# Backplane_PCB_Connector.net
KiCad netlist of a schematic drawn in Altium Designer
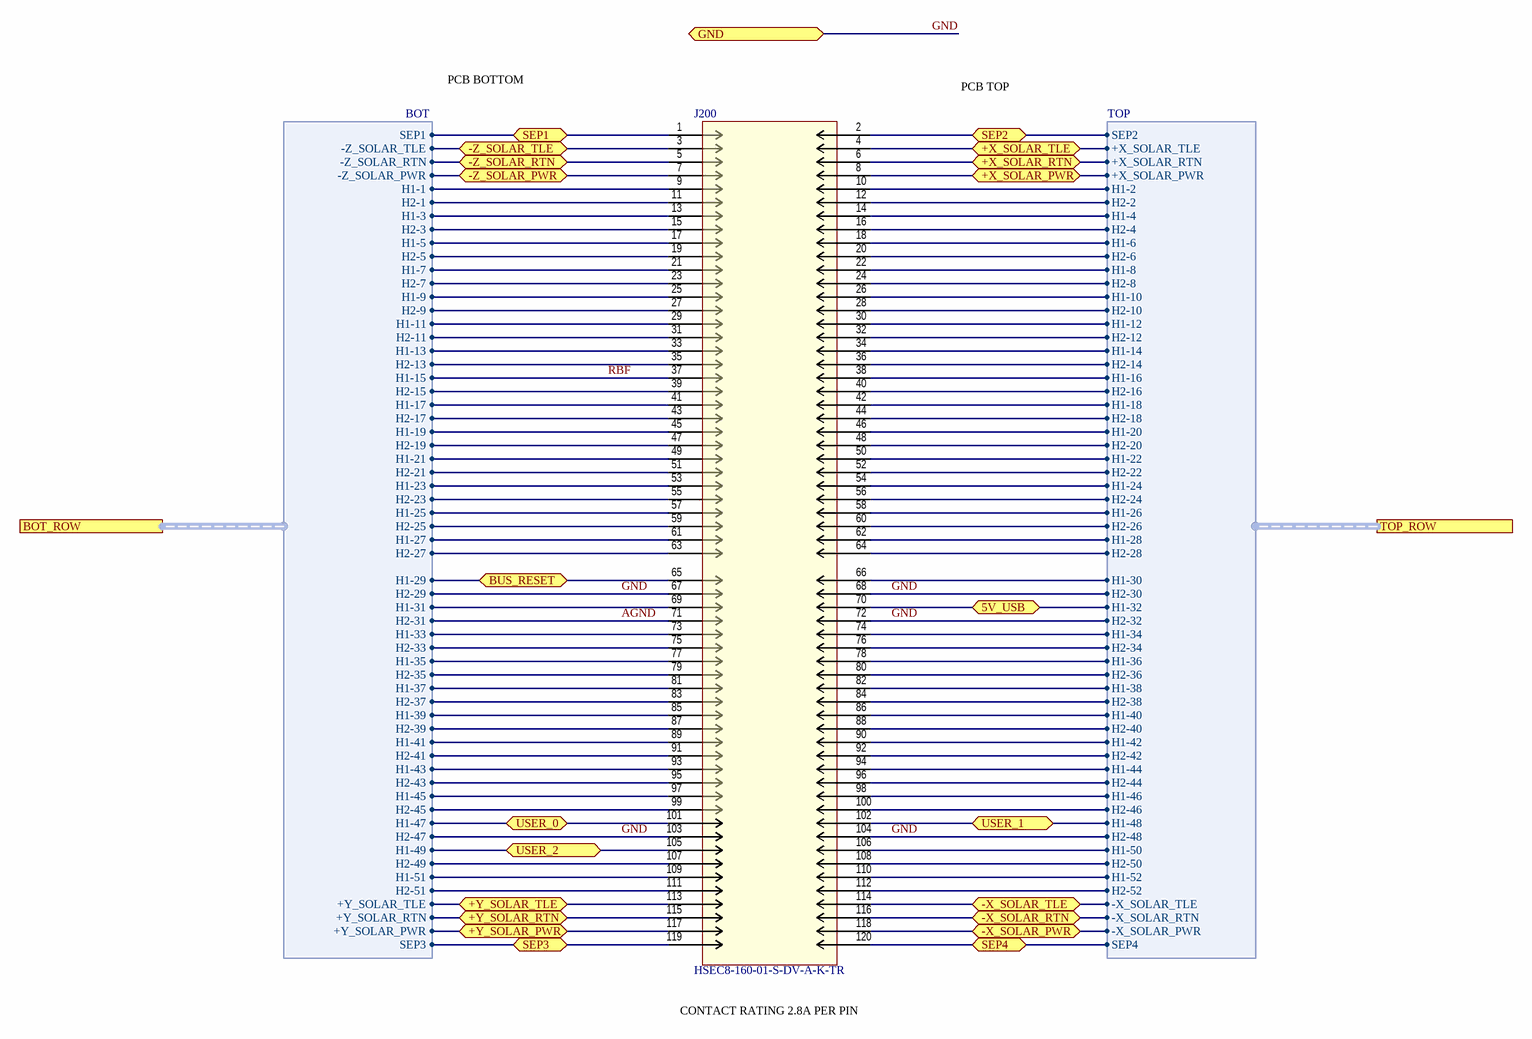
[diagram p0: Backplane PCB Connector.SchDoc]

(export (version "E")
  (design (tool "Eeschema 10.0.6"))
  (components
    (comp (ref "J200")
      (value "HSEC8-160-01-S-DV-A-K-TR")
      (footprint "HSEC8-160-01-S-DV-A-K-TR")
      (description "120 Position Female Connector Non Specified - Dual Edge Gold 0.031\" (0.80mm) Black")
      (fields (field (name "MANUFACTURER PART NUMBER 1") "HSEC8-160-01-S-DV-A-K-TR"))
      (libsource (lib "CubeSat-Backplane") (part "HSEC8-160-01-S-DV-A-K-TR"))
    )
  )
  (nets
    (net (code "3") (name "/+X_SOLAR_PWR") (class "Default")
      (node (ref "J200") (pin "8") (pinfunction "8_8") (pintype "passive"))
    )
    (net (code "4") (name "/+X_SOLAR_RTN") (class "Default")
      (node (ref "J200") (pin "6") (pinfunction "6_6") (pintype "passive"))
    )
    (net (code "5") (name "/+X_SOLAR_TLE") (class "Default")
      (node (ref "J200") (pin "4") (pinfunction "4_4") (pintype "passive"))
    )
    (net (code "6") (name "/+Y_SOLAR_PWR") (class "Default")
      (node (ref "J200") (pin "117") (pinfunction "117_117") (pintype "passive"))
    )
    (net (code "7") (name "/+Y_SOLAR_RTN") (class "Default")
      (node (ref "J200") (pin "115") (pinfunction "115_115") (pintype "passive"))
    )
    (net (code "8") (name "/+Y_SOLAR_TLE") (class "Default")
      (node (ref "J200") (pin "113") (pinfunction "113_113") (pintype "passive"))
    )
    (net (code "9") (name "/-X_SOLAR_PWR") (class "Default")
      (node (ref "J200") (pin "118") (pinfunction "118_118") (pintype "passive"))
    )
    (net (code "10") (name "/-X_SOLAR_RTN") (class "Default")
      (node (ref "J200") (pin "116") (pinfunction "116_116") (pintype "passive"))
    )
    (net (code "11") (name "/-X_SOLAR_TLE") (class "Default")
      (node (ref "J200") (pin "114") (pinfunction "114_114") (pintype "passive"))
    )
    (net (code "12") (name "/-Z_SOLAR_PWR") (class "Default")
      (node (ref "J200") (pin "7") (pinfunction "7_7") (pintype "passive"))
    )
    (net (code "13") (name "/-Z_SOLAR_RTN") (class "Default")
      (node (ref "J200") (pin "5") (pinfunction "5_5") (pintype "passive"))
    )
    (net (code "14") (name "/-Z_SOLAR_TLE") (class "Default")
      (node (ref "J200") (pin "3") (pinfunction "3_3") (pintype "passive"))
    )
    (net (code "15") (name "/5V_USB") (class "Default")
      (node (ref "J200") (pin "70") (pinfunction "70_70") (pintype "passive"))
    )
    (net (code "16") (name "/AGND") (class "Default")
      (node (ref "J200") (pin "71") (pinfunction "71_71") (pintype "passive"))
    )
    (net (code "17") (name "/BUS_RESET") (class "Default")
      (node (ref "J200") (pin "65") (pinfunction "65_65") (pintype "passive"))
    )
    (net (code "18") (name "/GND") (class "Default")
      (node (ref "J200") (pin "103") (pinfunction "103_103") (pintype "passive"))
      (node (ref "J200") (pin "104") (pinfunction "104_104") (pintype "passive"))
      (node (ref "J200") (pin "67") (pinfunction "67_67") (pintype "passive"))
      (node (ref "J200") (pin "68") (pinfunction "68_68") (pintype "passive"))
      (node (ref "J200") (pin "72") (pinfunction "72_72") (pintype "passive"))
    )
    (net (code "19") (name "/H1-1") (class "Default")
      (node (ref "J200") (pin "9") (pinfunction "9_9") (pintype "passive"))
    )
    (net (code "20") (name "/H1-2") (class "Default")
      (node (ref "J200") (pin "10") (pinfunction "10_10") (pintype "passive"))
    )
    (net (code "21") (name "/H1-3") (class "Default")
      (node (ref "J200") (pin "13") (pinfunction "13_13") (pintype "passive"))
    )
    (net (code "22") (name "/H1-4") (class "Default")
      (node (ref "J200") (pin "14") (pinfunction "14_14") (pintype "passive"))
    )
    (net (code "23") (name "/H1-5") (class "Default")
      (node (ref "J200") (pin "17") (pinfunction "17_17") (pintype "passive"))
    )
    (net (code "24") (name "/H1-6") (class "Default")
      (node (ref "J200") (pin "18") (pinfunction "18_18") (pintype "passive"))
    )
    (net (code "25") (name "/H1-7") (class "Default")
      (node (ref "J200") (pin "21") (pinfunction "21_21") (pintype "passive"))
    )
    (net (code "26") (name "/H1-8") (class "Default")
      (node (ref "J200") (pin "22") (pinfunction "22_22") (pintype "passive"))
    )
    (net (code "27") (name "/H1-9") (class "Default")
      (node (ref "J200") (pin "25") (pinfunction "25_25") (pintype "passive"))
    )
    (net (code "28") (name "/H1-10") (class "Default")
      (node (ref "J200") (pin "26") (pinfunction "26_26") (pintype "passive"))
    )
    (net (code "29") (name "/H1-11") (class "Default")
      (node (ref "J200") (pin "29") (pinfunction "29_29") (pintype "passive"))
    )
    (net (code "30") (name "/H1-12") (class "Default")
      (node (ref "J200") (pin "30") (pinfunction "30_30") (pintype "passive"))
    )
    (net (code "31") (name "/H1-13") (class "Default")
      (node (ref "J200") (pin "33") (pinfunction "33_33") (pintype "passive"))
    )
    (net (code "32") (name "/H1-14") (class "Default")
      (node (ref "J200") (pin "34") (pinfunction "34_34") (pintype "passive"))
    )
    (net (code "33") (name "/H1-16") (class "Default")
      (node (ref "J200") (pin "38") (pinfunction "38_38") (pintype "passive"))
    )
    (net (code "34") (name "/H1-17") (class "Default")
      (node (ref "J200") (pin "41") (pinfunction "41_41") (pintype "passive"))
    )
    (net (code "35") (name "/H1-18") (class "Default")
      (node (ref "J200") (pin "42") (pinfunction "42_42") (pintype "passive"))
    )
    (net (code "36") (name "/H1-19") (class "Default")
      (node (ref "J200") (pin "45") (pinfunction "45_45") (pintype "passive"))
    )
    (net (code "37") (name "/H1-20") (class "Default")
      (node (ref "J200") (pin "46") (pinfunction "46_46") (pintype "passive"))
    )
    (net (code "38") (name "/H1-21") (class "Default")
      (node (ref "J200") (pin "49") (pinfunction "49_49") (pintype "passive"))
    )
    (net (code "39") (name "/H1-22") (class "Default")
      (node (ref "J200") (pin "50") (pinfunction "50_50") (pintype "passive"))
    )
    (net (code "40") (name "/H1-23") (class "Default")
      (node (ref "J200") (pin "53") (pinfunction "53_53") (pintype "passive"))
    )
    (net (code "41") (name "/H1-24") (class "Default")
      (node (ref "J200") (pin "54") (pinfunction "54_54") (pintype "passive"))
    )
    (net (code "42") (name "/H1-25") (class "Default")
      (node (ref "J200") (pin "57") (pinfunction "57_57") (pintype "passive"))
    )
    (net (code "43") (name "/H1-26") (class "Default")
      (node (ref "J200") (pin "58") (pinfunction "58_58") (pintype "passive"))
    )
    (net (code "44") (name "/H1-27") (class "Default")
      (node (ref "J200") (pin "61") (pinfunction "61_61") (pintype "passive"))
    )
    (net (code "45") (name "/H1-28") (class "Default")
      (node (ref "J200") (pin "62") (pinfunction "62_62") (pintype "passive"))
    )
    (net (code "46") (name "/H1-30") (class "Default")
      (node (ref "J200") (pin "66") (pinfunction "66_66") (pintype "passive"))
    )
    (net (code "47") (name "/H1-31") (class "Default")
      (node (ref "J200") (pin "69") (pinfunction "69_69") (pintype "passive"))
    )
    (net (code "48") (name "/H1-33") (class "Default")
      (node (ref "J200") (pin "73") (pinfunction "73_73") (pintype "passive"))
    )
    (net (code "49") (name "/H1-34") (class "Default")
      (node (ref "J200") (pin "74") (pinfunction "74_74") (pintype "passive"))
    )
    (net (code "50") (name "/H1-35") (class "Default")
      (node (ref "J200") (pin "77") (pinfunction "77_77") (pintype "passive"))
    )
    (net (code "51") (name "/H1-36") (class "Default")
      (node (ref "J200") (pin "78") (pinfunction "78_78") (pintype "passive"))
    )
    (net (code "52") (name "/H1-37") (class "Default")
      (node (ref "J200") (pin "81") (pinfunction "81_81") (pintype "passive"))
    )
    (net (code "53") (name "/H1-38") (class "Default")
      (node (ref "J200") (pin "82") (pinfunction "82_82") (pintype "passive"))
    )
    (net (code "54") (name "/H1-39") (class "Default")
      (node (ref "J200") (pin "85") (pinfunction "85_85") (pintype "passive"))
    )
    (net (code "55") (name "/H1-40") (class "Default")
      (node (ref "J200") (pin "86") (pinfunction "86_86") (pintype "passive"))
    )
    (net (code "56") (name "/H1-41") (class "Default")
      (node (ref "J200") (pin "89") (pinfunction "89_89") (pintype "passive"))
    )
    (net (code "57") (name "/H1-42") (class "Default")
      (node (ref "J200") (pin "90") (pinfunction "90_90") (pintype "passive"))
    )
    (net (code "58") (name "/H1-43") (class "Default")
      (node (ref "J200") (pin "93") (pinfunction "93_93") (pintype "passive"))
    )
    (net (code "59") (name "/H1-44") (class "Default")
      (node (ref "J200") (pin "94") (pinfunction "94_94") (pintype "passive"))
    )
    (net (code "60") (name "/H1-45") (class "Default")
      (node (ref "J200") (pin "97") (pinfunction "97_97") (pintype "passive"))
    )
    (net (code "61") (name "/H1-46") (class "Default")
      (node (ref "J200") (pin "98") (pinfunction "98_98") (pintype "passive"))
    )
    (net (code "62") (name "/H1-50") (class "Default")
      (node (ref "J200") (pin "106") (pinfunction "106_106") (pintype "passive"))
    )
    (net (code "63") (name "/H1-51") (class "Default")
      (node (ref "J200") (pin "109") (pinfunction "109_109") (pintype "passive"))
    )
    (net (code "64") (name "/H1-52") (class "Default")
      (node (ref "J200") (pin "110") (pinfunction "110_110") (pintype "passive"))
    )
    (net (code "65") (name "/H2-1") (class "Default")
      (node (ref "J200") (pin "11") (pinfunction "11_11") (pintype "passive"))
    )
    (net (code "66") (name "/H2-2") (class "Default")
      (node (ref "J200") (pin "12") (pinfunction "12_12") (pintype "passive"))
    )
    (net (code "67") (name "/H2-3") (class "Default")
      (node (ref "J200") (pin "15") (pinfunction "15_15") (pintype "passive"))
    )
    (net (code "68") (name "/H2-4") (class "Default")
      (node (ref "J200") (pin "16") (pinfunction "16_16") (pintype "passive"))
    )
    (net (code "69") (name "/H2-5") (class "Default")
      (node (ref "J200") (pin "19") (pinfunction "19_19") (pintype "passive"))
    )
    (net (code "70") (name "/H2-6") (class "Default")
      (node (ref "J200") (pin "20") (pinfunction "20_20") (pintype "passive"))
    )
    (net (code "71") (name "/H2-7") (class "Default")
      (node (ref "J200") (pin "23") (pinfunction "23_23") (pintype "passive"))
    )
    (net (code "72") (name "/H2-8") (class "Default")
      (node (ref "J200") (pin "24") (pinfunction "24_24") (pintype "passive"))
    )
    (net (code "73") (name "/H2-9") (class "Default")
      (node (ref "J200") (pin "27") (pinfunction "27_27") (pintype "passive"))
    )
    (net (code "74") (name "/H2-10") (class "Default")
      (node (ref "J200") (pin "28") (pinfunction "28_28") (pintype "passive"))
    )
    (net (code "75") (name "/H2-11") (class "Default")
      (node (ref "J200") (pin "31") (pinfunction "31_31") (pintype "passive"))
    )
    (net (code "76") (name "/H2-12") (class "Default")
      (node (ref "J200") (pin "32") (pinfunction "32_32") (pintype "passive"))
    )
    (net (code "77") (name "/H2-13") (class "Default")
      (node (ref "J200") (pin "35") (pinfunction "35_35") (pintype "passive"))
    )
    (net (code "78") (name "/H2-14") (class "Default")
      (node (ref "J200") (pin "36") (pinfunction "36_36") (pintype "passive"))
    )
    (net (code "79") (name "/H2-15") (class "Default")
      (node (ref "J200") (pin "39") (pinfunction "39_39") (pintype "passive"))
    )
    (net (code "80") (name "/H2-16") (class "Default")
      (node (ref "J200") (pin "40") (pinfunction "40_40") (pintype "passive"))
    )
    (net (code "81") (name "/H2-17") (class "Default")
      (node (ref "J200") (pin "43") (pinfunction "43_43") (pintype "passive"))
    )
    (net (code "82") (name "/H2-18") (class "Default")
      (node (ref "J200") (pin "44") (pinfunction "44_44") (pintype "passive"))
    )
    (net (code "83") (name "/H2-19") (class "Default")
      (node (ref "J200") (pin "47") (pinfunction "47_47") (pintype "passive"))
    )
    (net (code "84") (name "/H2-20") (class "Default")
      (node (ref "J200") (pin "48") (pinfunction "48_48") (pintype "passive"))
    )
    (net (code "85") (name "/H2-21") (class "Default")
      (node (ref "J200") (pin "51") (pinfunction "51_51") (pintype "passive"))
    )
    (net (code "86") (name "/H2-22") (class "Default")
      (node (ref "J200") (pin "52") (pinfunction "52_52") (pintype "passive"))
    )
    (net (code "87") (name "/H2-23") (class "Default")
      (node (ref "J200") (pin "55") (pinfunction "55_55") (pintype "passive"))
    )
    (net (code "88") (name "/H2-24") (class "Default")
      (node (ref "J200") (pin "56") (pinfunction "56_56") (pintype "passive"))
    )
    (net (code "89") (name "/H2-25") (class "Default")
      (node (ref "J200") (pin "59") (pinfunction "59_59") (pintype "passive"))
    )
    (net (code "90") (name "/H2-26") (class "Default")
      (node (ref "J200") (pin "60") (pinfunction "60_60") (pintype "passive"))
    )
    (net (code "91") (name "/H2-27") (class "Default")
      (node (ref "J200") (pin "63") (pinfunction "63_63") (pintype "passive"))
    )
    (net (code "92") (name "/H2-28") (class "Default")
      (node (ref "J200") (pin "64") (pinfunction "64_64") (pintype "passive"))
    )
    (net (code "93") (name "/H2-33") (class "Default")
      (node (ref "J200") (pin "75") (pinfunction "75_75") (pintype "passive"))
    )
    (net (code "94") (name "/H2-34") (class "Default")
      (node (ref "J200") (pin "76") (pinfunction "76_76") (pintype "passive"))
    )
    (net (code "95") (name "/H2-35") (class "Default")
      (node (ref "J200") (pin "79") (pinfunction "79_79") (pintype "passive"))
    )
    (net (code "96") (name "/H2-36") (class "Default")
      (node (ref "J200") (pin "80") (pinfunction "80_80") (pintype "passive"))
    )
    (net (code "97") (name "/H2-37") (class "Default")
      (node (ref "J200") (pin "83") (pinfunction "83_83") (pintype "passive"))
    )
    (net (code "98") (name "/H2-38") (class "Default")
      (node (ref "J200") (pin "84") (pinfunction "84_84") (pintype "passive"))
    )
    (net (code "99") (name "/H2-39") (class "Default")
      (node (ref "J200") (pin "87") (pinfunction "87_87") (pintype "passive"))
    )
    (net (code "100") (name "/H2-40") (class "Default")
      (node (ref "J200") (pin "88") (pinfunction "88_88") (pintype "passive"))
    )
    (net (code "101") (name "/H2-41") (class "Default")
      (node (ref "J200") (pin "91") (pinfunction "91_91") (pintype "passive"))
    )
    (net (code "102") (name "/H2-42") (class "Default")
      (node (ref "J200") (pin "92") (pinfunction "92_92") (pintype "passive"))
    )
    (net (code "103") (name "/H2-43") (class "Default")
      (node (ref "J200") (pin "95") (pinfunction "95_95") (pintype "passive"))
    )
    (net (code "104") (name "/H2-44") (class "Default")
      (node (ref "J200") (pin "96") (pinfunction "96_96") (pintype "passive"))
    )
    (net (code "105") (name "/H2-45") (class "Default")
      (node (ref "J200") (pin "99") (pinfunction "99_99") (pintype "passive"))
    )
    (net (code "106") (name "/H2-46") (class "Default")
      (node (ref "J200") (pin "100") (pinfunction "100_100") (pintype "passive"))
    )
    (net (code "107") (name "/H2-49") (class "Default")
      (node (ref "J200") (pin "107") (pinfunction "107_107") (pintype "passive"))
    )
    (net (code "108") (name "/H2-50") (class "Default")
      (node (ref "J200") (pin "108") (pinfunction "108_108") (pintype "passive"))
    )
    (net (code "109") (name "/H2-51") (class "Default")
      (node (ref "J200") (pin "111") (pinfunction "111_111") (pintype "passive"))
    )
    (net (code "110") (name "/H2-52") (class "Default")
      (node (ref "J200") (pin "112") (pinfunction "112_112") (pintype "passive"))
    )
    (net (code "111") (name "/RBF") (class "Default")
      (node (ref "J200") (pin "37") (pinfunction "37_37") (pintype "passive"))
    )
    (net (code "112") (name "/SEP1") (class "Default")
      (node (ref "J200") (pin "1") (pinfunction "1_1") (pintype "passive"))
    )
    (net (code "113") (name "/SEP2") (class "Default")
      (node (ref "J200") (pin "2") (pinfunction "2_2") (pintype "passive"))
    )
    (net (code "114") (name "/SEP3") (class "Default")
      (node (ref "J200") (pin "119") (pinfunction "119_119") (pintype "passive"))
    )
    (net (code "115") (name "/SEP4") (class "Default")
      (node (ref "J200") (pin "120") (pinfunction "120_120") (pintype "passive"))
    )
    (net (code "116") (name "/USER_0") (class "Default")
      (node (ref "J200") (pin "101") (pinfunction "101_101") (pintype "passive"))
    )
    (net (code "117") (name "/USER_1") (class "Default")
      (node (ref "J200") (pin "102") (pinfunction "102_102") (pintype "passive"))
    )
    (net (code "118") (name "/USER_2") (class "Default")
      (node (ref "J200") (pin "105") (pinfunction "105_105") (pintype "passive"))
    )
  )
)
